# arduino-pro-mini_2-way-switches_v0_2_5_N.net
KiCad netlist of a schematic drawn in EAGLE
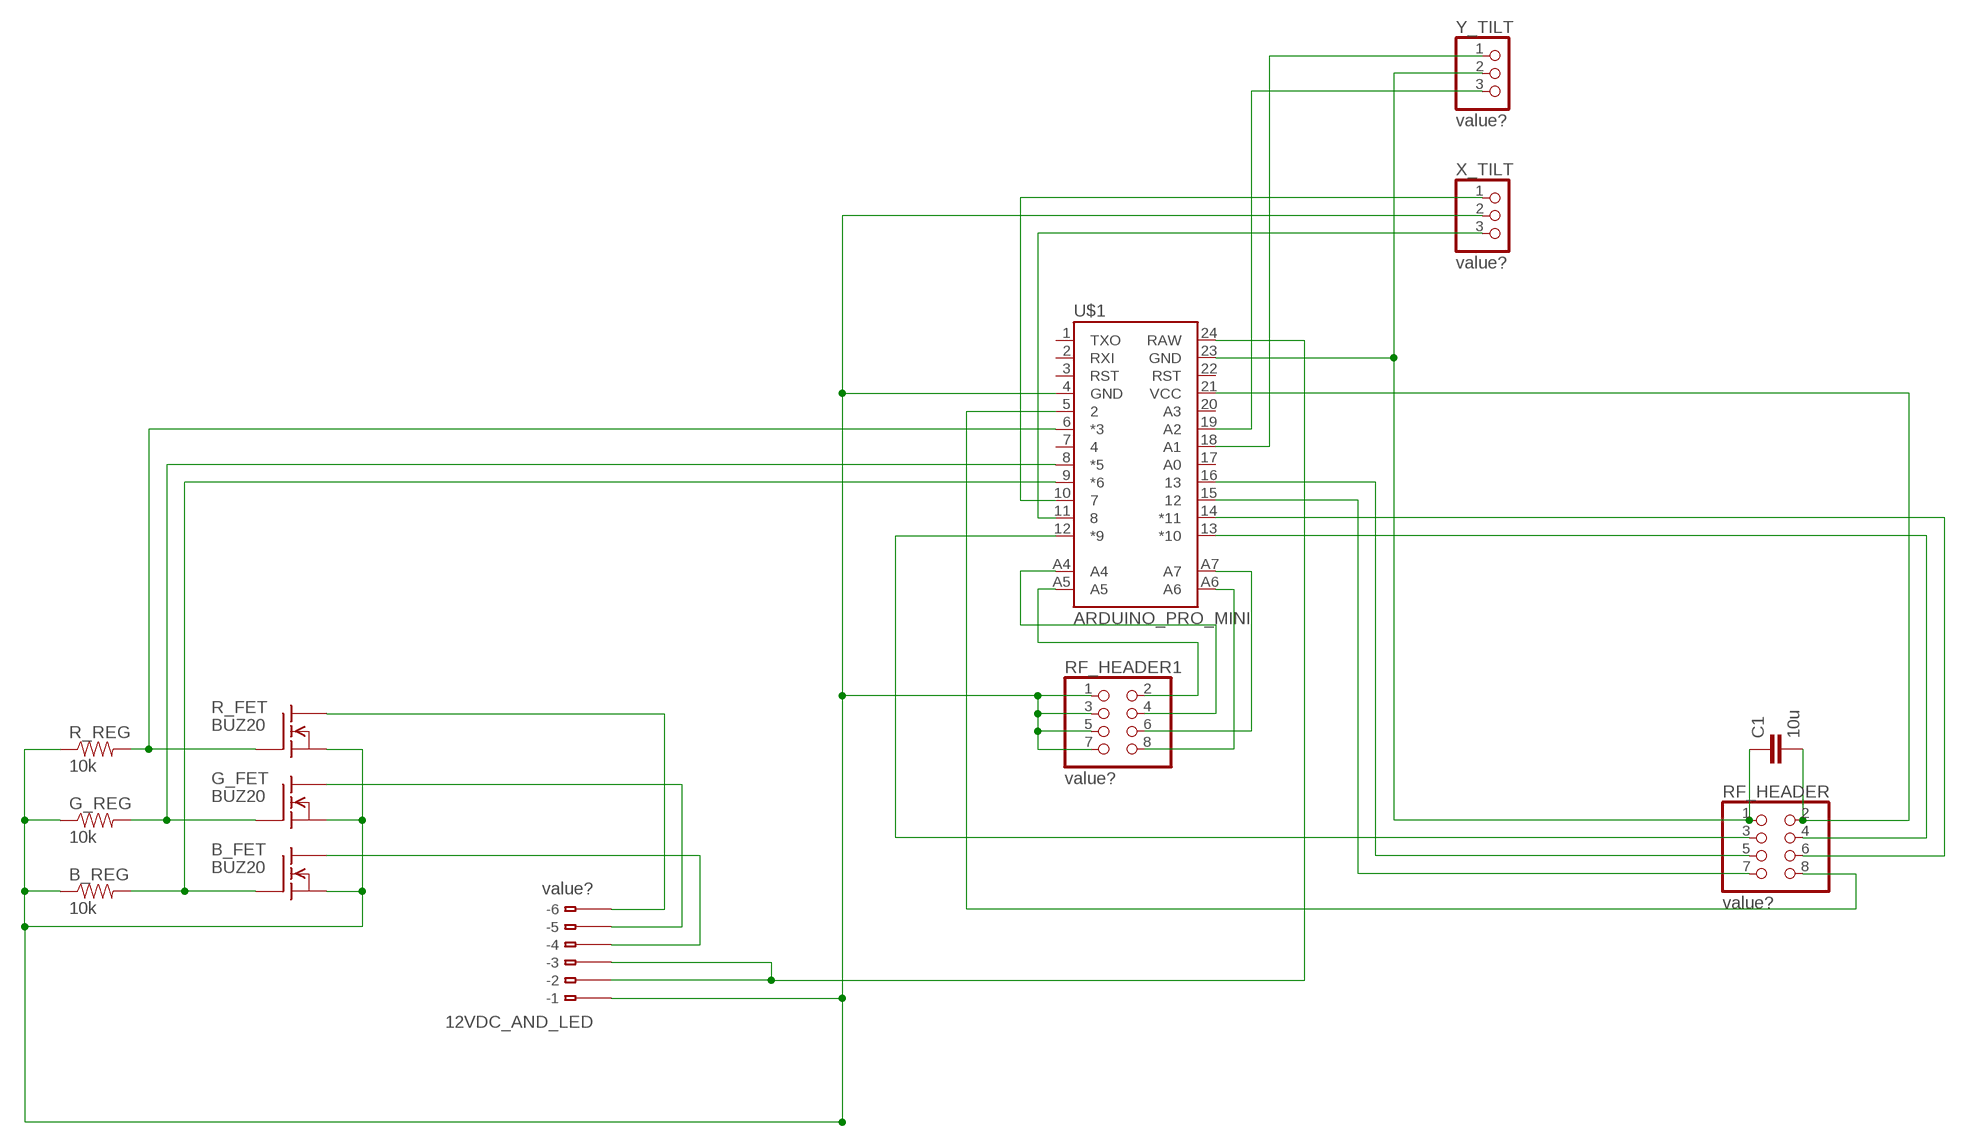
[diagram p0: schematic, sheet 1]

(export (version "E")
  (design (tool "Eeschema 10.0.6"))
  (components
    (comp (ref "12VDC_AND_LED")
      (value "value?")
      (footprint "eagle-import:234-206")
      (fields (field (name "MPN") "234-206"))
      (libsource (lib "eagle-import") (part "234-206"))
    )
    (comp (ref "B_FET")
      (value "BUZ20")
      (footprint "eagle-import:TO220")
      (libsource (lib "eagle-import") (part "BUZ20"))
    )
    (comp (ref "B_REG")
      (value "10k")
      (footprint "eagle-import:AXIAL-0.4")
      (libsource (lib "eagle-import") (part "RESISTORPTH-1/4W"))
    )
    (comp (ref "C1")
      (value "10u")
      (footprint "eagle-import:CAP-PTH-SMALL")
      (libsource (lib "eagle-import") (part "CAPPTH"))
    )
    (comp (ref "G_FET")
      (value "BUZ20")
      (footprint "eagle-import:TO220")
      (libsource (lib "eagle-import") (part "BUZ20"))
    )
    (comp (ref "G_REG")
      (value "10k")
      (footprint "eagle-import:AXIAL-0.4")
      (libsource (lib "eagle-import") (part "RESISTORPTH-1/4W"))
    )
    (comp (ref "RF_HEADER")
      (value "value?")
      (footprint "eagle-import:2X04")
      (libsource (lib "eagle-import") (part "PINHD-2X4"))
    )
    (comp (ref "RF_HEADER1")
      (value "value?")
      (footprint "eagle-import:2X04")
      (libsource (lib "eagle-import") (part "PINHD-2X4"))
    )
    (comp (ref "R_FET")
      (value "BUZ20")
      (footprint "eagle-import:TO220")
      (libsource (lib "eagle-import") (part "BUZ20"))
    )
    (comp (ref "R_REG")
      (value "10k")
      (footprint "eagle-import:AXIAL-0.4")
      (libsource (lib "eagle-import") (part "RESISTORPTH-1/4W"))
    )
    (comp (ref "U$1")
      (value "ARDUINO_PRO_MINI")
      (footprint "eagle-import:ARDUINO_PRO_MINI")
      (libsource (lib "eagle-import") (part "ARDUINO_PRO_MINI"))
    )
    (comp (ref "X_TILT")
      (value "value?")
      (footprint "eagle-import:1X03")
      (libsource (lib "eagle-import") (part "PINHD-1X3"))
    )
    (comp (ref "Y_TILT")
      (value "value?")
      (footprint "eagle-import:1X03")
      (libsource (lib "eagle-import") (part "PINHD-1X3"))
    )
  )
  (nets
    (net (code "1") (name "Net-(12VDC_AND_LED-B-1)") (class "Default")
      (node (ref "12VDC_AND_LED") (pin "B1") (pinfunction "B-1_B1") (pintype "passive"))
      (node (ref "B_FET") (pin "3") (pinfunction "S_3") (pintype "passive"))
      (node (ref "B_REG") (pin "P$1") (pinfunction "1_P$1") (pintype "passive"))
      (node (ref "G_FET") (pin "3") (pinfunction "S_3") (pintype "passive"))
      (node (ref "G_REG") (pin "P$1") (pinfunction "1_P$1") (pintype "passive"))
      (node (ref "RF_HEADER1") (pin "1") (pinfunction "1_1") (pintype "passive"))
      (node (ref "RF_HEADER1") (pin "3") (pinfunction "3_3") (pintype "passive"))
      (node (ref "RF_HEADER1") (pin "5") (pinfunction "5_5") (pintype "passive"))
      (node (ref "RF_HEADER1") (pin "7") (pinfunction "7_7") (pintype "passive"))
      (node (ref "R_FET") (pin "3") (pinfunction "S_3") (pintype "passive"))
      (node (ref "R_REG") (pin "P$1") (pinfunction "1_P$1") (pintype "passive"))
      (node (ref "U$1") (pin "4") (pinfunction "GND_4") (pintype "bidirectional"))
      (node (ref "X_TILT") (pin "2") (pinfunction "2_2") (pintype "passive"))
    )
    (net (code "2") (name "Net-(12VDC_AND_LED-B-2)") (class "Default")
      (node (ref "12VDC_AND_LED") (pin "B2") (pinfunction "B-2_B2") (pintype "passive"))
      (node (ref "12VDC_AND_LED") (pin "B3") (pinfunction "B-3_B3") (pintype "passive"))
      (node (ref "U$1") (pin "24") (pinfunction "RAW_24") (pintype "bidirectional"))
    )
    (net (code "3") (name "Net-(12VDC_AND_LED-B-4)") (class "Default")
      (node (ref "12VDC_AND_LED") (pin "B4") (pinfunction "B-4_B4") (pintype "passive"))
      (node (ref "B_FET") (pin "2") (pinfunction "D_2") (pintype "passive"))
    )
    (net (code "4") (name "Net-(12VDC_AND_LED-B-5)") (class "Default")
      (node (ref "12VDC_AND_LED") (pin "B5") (pinfunction "B-5_B5") (pintype "passive"))
      (node (ref "G_FET") (pin "2") (pinfunction "D_2") (pintype "passive"))
    )
    (net (code "5") (name "Net-(12VDC_AND_LED-B-6)") (class "Default")
      (node (ref "12VDC_AND_LED") (pin "B6") (pinfunction "B-6_B6") (pintype "passive"))
      (node (ref "R_FET") (pin "2") (pinfunction "D_2") (pintype "passive"))
    )
    (net (code "6") (name "Net-(B_FET-G)") (class "Default")
      (node (ref "B_FET") (pin "1") (pinfunction "G_1") (pintype "passive"))
      (node (ref "B_REG") (pin "P$2") (pinfunction "2_P$2") (pintype "passive"))
      (node (ref "U$1") (pin "9") (pinfunction "*6_9") (pintype "bidirectional"))
    )
    (net (code "7") (name "Net-(C1-Pad1)") (class "Default")
      (node (ref "C1") (pin "1") (pinfunction "1_1") (pintype "passive"))
      (node (ref "RF_HEADER") (pin "1") (pinfunction "1_1") (pintype "passive"))
      (node (ref "U$1") (pin "23") (pinfunction "GND_23") (pintype "bidirectional"))
      (node (ref "Y_TILT") (pin "2") (pinfunction "2_2") (pintype "passive"))
    )
    (net (code "8") (name "Net-(G_FET-G)") (class "Default")
      (node (ref "G_FET") (pin "1") (pinfunction "G_1") (pintype "passive"))
      (node (ref "G_REG") (pin "P$2") (pinfunction "2_P$2") (pintype "passive"))
      (node (ref "U$1") (pin "8") (pinfunction "*5_8") (pintype "bidirectional"))
    )
    (net (code "9") (name "Net-(RF_HEADER1-Pad2)") (class "Default")
      (node (ref "RF_HEADER1") (pin "2") (pinfunction "2_2") (pintype "passive"))
      (node (ref "U$1") (pin "A5") (pinfunction "A5_A5") (pintype "bidirectional"))
    )
    (net (code "10") (name "Net-(RF_HEADER1-Pad4)") (class "Default")
      (node (ref "RF_HEADER1") (pin "4") (pinfunction "4_4") (pintype "passive"))
      (node (ref "U$1") (pin "A4") (pinfunction "A4_A4") (pintype "bidirectional"))
    )
    (net (code "11") (name "Net-(RF_HEADER1-Pad6)") (class "Default")
      (node (ref "RF_HEADER1") (pin "6") (pinfunction "6_6") (pintype "passive"))
      (node (ref "U$1") (pin "A7") (pinfunction "A7_A7") (pintype "bidirectional"))
    )
    (net (code "12") (name "Net-(RF_HEADER1-Pad8)") (class "Default")
      (node (ref "RF_HEADER1") (pin "8") (pinfunction "8_8") (pintype "passive"))
      (node (ref "U$1") (pin "A6") (pinfunction "A6_A6") (pintype "bidirectional"))
    )
    (net (code "13") (name "Net-(R_FET-G)") (class "Default")
      (node (ref "R_FET") (pin "1") (pinfunction "G_1") (pintype "passive"))
      (node (ref "R_REG") (pin "P$2") (pinfunction "2_P$2") (pintype "passive"))
      (node (ref "U$1") (pin "6") (pinfunction "*3_6") (pintype "bidirectional"))
    )
    (net (code "14") (name "Net-(U$1-*9)") (class "Default")
      (node (ref "RF_HEADER") (pin "3") (pinfunction "3_3") (pintype "passive"))
      (node (ref "U$1") (pin "12") (pinfunction "*9_12") (pintype "bidirectional"))
    )
    (net (code "15") (name "Net-(U$1-*10)") (class "Default")
      (node (ref "RF_HEADER") (pin "4") (pinfunction "4_4") (pintype "passive"))
      (node (ref "U$1") (pin "13") (pinfunction "*10_13") (pintype "bidirectional"))
    )
    (net (code "16") (name "Net-(U$1-*11)") (class "Default")
      (node (ref "RF_HEADER") (pin "6") (pinfunction "6_6") (pintype "passive"))
      (node (ref "U$1") (pin "14") (pinfunction "*11_14") (pintype "bidirectional"))
    )
    (net (code "17") (name "Net-(U$1-2)") (class "Default")
      (node (ref "RF_HEADER") (pin "8") (pinfunction "8_8") (pintype "passive"))
      (node (ref "U$1") (pin "5") (pinfunction "2_5") (pintype "bidirectional"))
    )
    (net (code "18") (name "Net-(U$1-7)") (class "Default")
      (node (ref "U$1") (pin "10") (pinfunction "7_10") (pintype "bidirectional"))
      (node (ref "X_TILT") (pin "1") (pinfunction "1_1") (pintype "passive"))
    )
    (net (code "19") (name "Net-(U$1-8)") (class "Default")
      (node (ref "U$1") (pin "11") (pinfunction "8_11") (pintype "bidirectional"))
      (node (ref "X_TILT") (pin "3") (pinfunction "3_3") (pintype "passive"))
    )
    (net (code "20") (name "Net-(U$1-12)") (class "Default")
      (node (ref "RF_HEADER") (pin "7") (pinfunction "7_7") (pintype "passive"))
      (node (ref "U$1") (pin "15") (pinfunction "12_15") (pintype "bidirectional"))
    )
    (net (code "21") (name "Net-(U$1-13)") (class "Default")
      (node (ref "RF_HEADER") (pin "5") (pinfunction "5_5") (pintype "passive"))
      (node (ref "U$1") (pin "16") (pinfunction "13_16") (pintype "bidirectional"))
    )
    (net (code "22") (name "Net-(U$1-A1)") (class "Default")
      (node (ref "U$1") (pin "18") (pinfunction "A1_18") (pintype "bidirectional"))
      (node (ref "Y_TILT") (pin "1") (pinfunction "1_1") (pintype "passive"))
    )
    (net (code "23") (name "Net-(U$1-A2)") (class "Default")
      (node (ref "U$1") (pin "19") (pinfunction "A2_19") (pintype "bidirectional"))
      (node (ref "Y_TILT") (pin "3") (pinfunction "3_3") (pintype "passive"))
    )
    (net (code "24") (name "Net-(U$1-VCC)") (class "Default")
      (node (ref "C1") (pin "2") (pinfunction "2_2") (pintype "passive"))
      (node (ref "RF_HEADER") (pin "2") (pinfunction "2_2") (pintype "passive"))
      (node (ref "U$1") (pin "21") (pinfunction "VCC_21") (pintype "bidirectional"))
    )
    (net (code "25") (name "unconnected-(12VDC_AND_LED--1-PadA1)") (class "Default")
      (node (ref "12VDC_AND_LED") (pin "A1") (pinfunction "-1_A1") (pintype "passive"))
    )
    (net (code "26") (name "unconnected-(12VDC_AND_LED--2-PadA2)") (class "Default")
      (node (ref "12VDC_AND_LED") (pin "A2") (pinfunction "-2_A2") (pintype "passive"))
    )
    (net (code "27") (name "unconnected-(12VDC_AND_LED--3-PadA3)") (class "Default")
      (node (ref "12VDC_AND_LED") (pin "A3") (pinfunction "-3_A3") (pintype "passive"))
    )
    (net (code "28") (name "unconnected-(12VDC_AND_LED--4-PadA4)") (class "Default")
      (node (ref "12VDC_AND_LED") (pin "A4") (pinfunction "-4_A4") (pintype "passive"))
    )
    (net (code "29") (name "unconnected-(12VDC_AND_LED--5-PadA5)") (class "Default")
      (node (ref "12VDC_AND_LED") (pin "A5") (pinfunction "-5_A5") (pintype "passive"))
    )
    (net (code "30") (name "unconnected-(12VDC_AND_LED--6-PadA6)") (class "Default")
      (node (ref "12VDC_AND_LED") (pin "A6") (pinfunction "-6_A6") (pintype "passive"))
    )
    (net (code "31") (name "unconnected-(U$1-4-Pad7)") (class "Default")
      (node (ref "U$1") (pin "7") (pinfunction "4_7") (pintype "bidirectional"))
    )
    (net (code "32") (name "unconnected-(U$1-A0-Pad17)") (class "Default")
      (node (ref "U$1") (pin "17") (pinfunction "A0_17") (pintype "bidirectional"))
    )
    (net (code "33") (name "unconnected-(U$1-A3-Pad20)") (class "Default")
      (node (ref "U$1") (pin "20") (pinfunction "A3_20") (pintype "bidirectional"))
    )
    (net (code "34") (name "unconnected-(U$1-RST-Pad3)") (class "Default")
      (node (ref "U$1") (pin "3") (pinfunction "RST_3") (pintype "bidirectional"))
    )
    (net (code "35") (name "unconnected-(U$1-RST-Pad22)") (class "Default")
      (node (ref "U$1") (pin "22") (pinfunction "RST_22") (pintype "bidirectional"))
    )
    (net (code "36") (name "unconnected-(U$1-RXI-Pad2)") (class "Default")
      (node (ref "U$1") (pin "2") (pinfunction "RXI_2") (pintype "bidirectional"))
    )
    (net (code "37") (name "unconnected-(U$1-TXO-Pad1)") (class "Default")
      (node (ref "U$1") (pin "1") (pinfunction "TXO_1") (pintype "bidirectional"))
    )
  )
)
